# InverterTranslation.net
KiCad netlist of a schematic drawn in Altium Designer
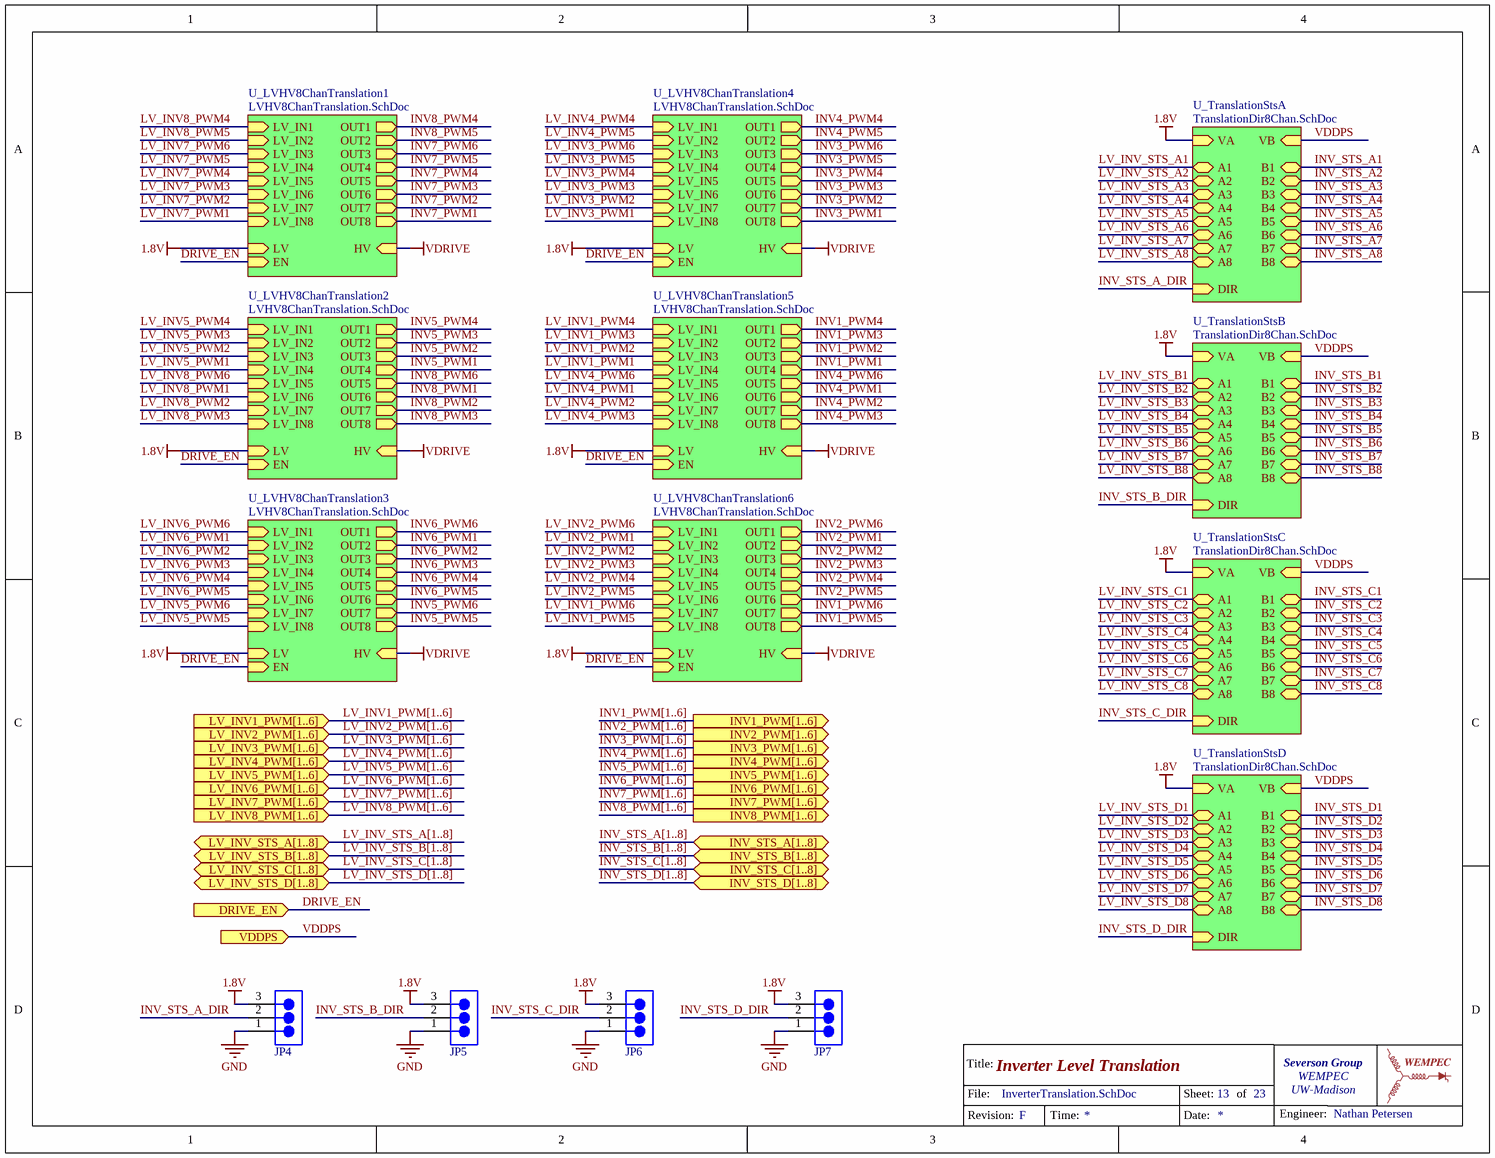
[diagram p0: InverterTranslation.SchDoc]

(export (version "E")
  (design (tool "Eeschema 10.0.6"))
  (components
    (comp (ref "JP4")
      (value "Jumper3")
      (footprint "PIN_HEADER_1X3")
      (libsource (lib "AMDC") (part "Jumper3"))
    )
    (comp (ref "JP5")
      (value "Jumper3")
      (footprint "PIN_HEADER_1X3")
      (libsource (lib "AMDC") (part "Jumper3"))
    )
    (comp (ref "JP6")
      (value "Jumper3")
      (footprint "PIN_HEADER_1X3")
      (libsource (lib "AMDC") (part "Jumper3"))
    )
    (comp (ref "JP7")
      (value "Jumper3")
      (footprint "PIN_HEADER_1X3")
      (libsource (lib "AMDC") (part "Jumper3"))
    )
  )
  (nets
    (net (code "67") (name "/INV_STS_A_DIR") (class "Default")
      (node (ref "JP4") (pin "2") (pinfunction "75_2") (pintype "passive"))
    )
    (net (code "77") (name "/INV_STS_B_DIR") (class "Default")
      (node (ref "JP5") (pin "2") (pinfunction "75_2") (pintype "passive"))
    )
    (net (code "87") (name "/INV_STS_C_DIR") (class "Default")
      (node (ref "JP6") (pin "2") (pinfunction "75_2") (pintype "passive"))
    )
    (net (code "97") (name "/INV_STS_D_DIR") (class "Default")
      (node (ref "JP7") (pin "2") (pinfunction "75_2") (pintype "passive"))
    )
    (net (code "191") (name "1.8V") (class "Default")
      (node (ref "JP4") (pin "3") (pinfunction "75_3") (pintype "passive"))
      (node (ref "JP5") (pin "3") (pinfunction "75_3") (pintype "passive"))
      (node (ref "JP6") (pin "3") (pinfunction "75_3") (pintype "passive"))
      (node (ref "JP7") (pin "3") (pinfunction "75_3") (pintype "passive"))
    )
    (net (code "192") (name "GND") (class "Default")
      (node (ref "JP4") (pin "1") (pinfunction "76_1") (pintype "passive"))
      (node (ref "JP5") (pin "1") (pinfunction "76_1") (pintype "passive"))
      (node (ref "JP6") (pin "1") (pinfunction "76_1") (pintype "passive"))
      (node (ref "JP7") (pin "1") (pinfunction "76_1") (pintype "passive"))
    )
  )
)
